# SpaceInvaders-v30.net
KiCad netlist of a schematic drawn in EAGLE
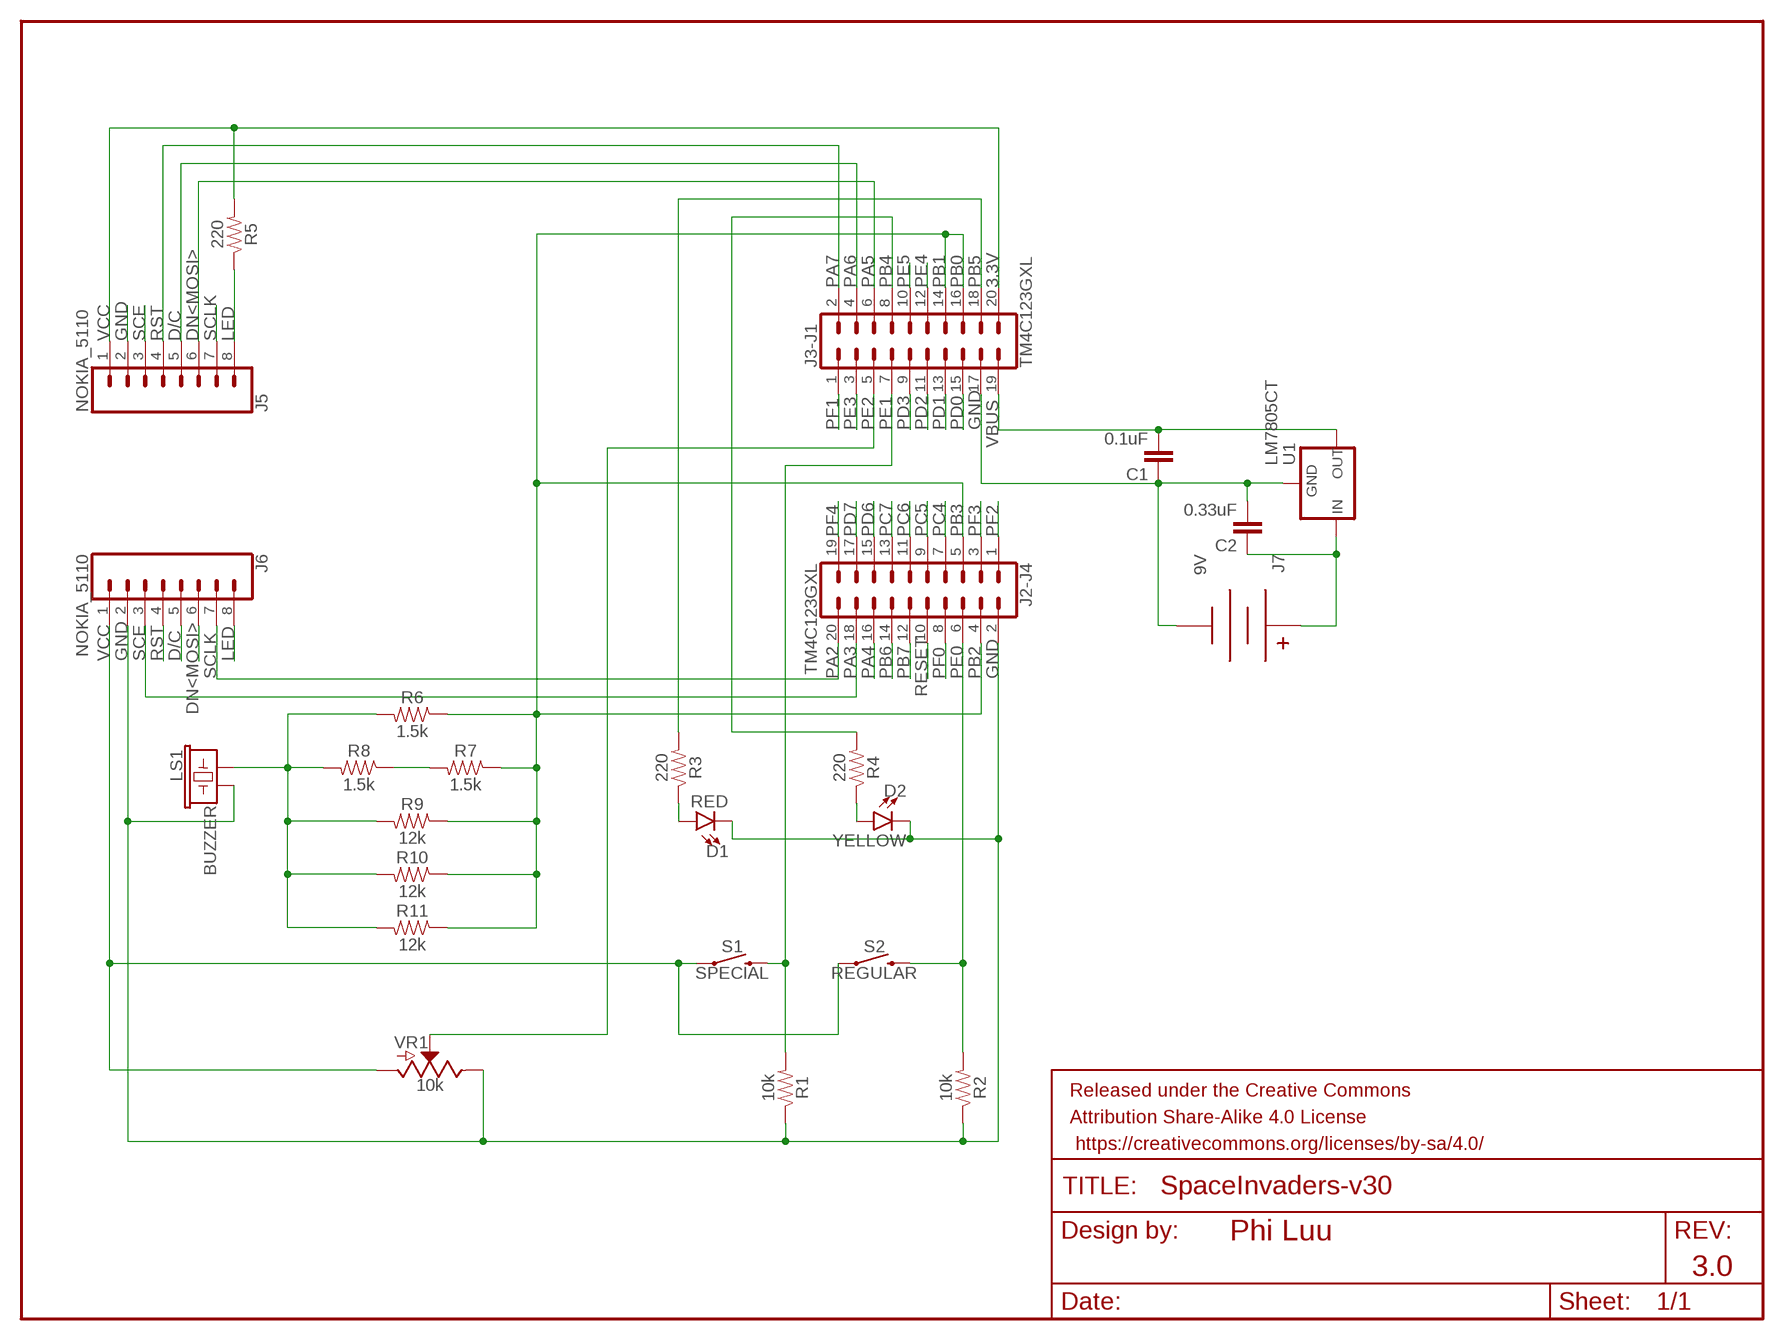
[diagram p0: schematic, sheet 1]

(export (version "E")
  (design (tool "Eeschema 10.0.6"))
  (components
    (comp (ref "C1")
      (value "0.1uF")
      (footprint "eagle-import:CAP-PTH-SMALL-KIT")
      (libsource (lib "eagle-import") (part "0.1UF-KIT-EZ-50V-20%"))
    )
    (comp (ref "C2")
      (value "0.33uF")
      (footprint "eagle-import:CAP-PTH-SMALL-KIT")
      (libsource (lib "eagle-import") (part "0.1UF-KIT-EZ-50V-20%"))
    )
    (comp (ref "D1")
      (value "RED")
      (footprint "eagle-import:LED_5MM")
      (libsource (lib "eagle-import") (part "LED5MM"))
    )
    (comp (ref "D2")
      (value "YELLOW")
      (footprint "eagle-import:LED_5MM")
      (libsource (lib "eagle-import") (part "LED5MM"))
    )
    (comp (ref "FRAME1")
      (value "FRAME-LETTER")
      (footprint "eagle-import:CREATIVE_COMMONS")
      (libsource (lib "eagle-import") (part "FRAME-LETTER"))
    )
    (comp (ref "J2-J4")
      (value "TM4C123GXL")
      (footprint "eagle-import:2X10")
      (libsource (lib "eagle-import") (part "CONN_10X2"))
    )
    (comp (ref "J3-J1")
      (value "TM4C123GXL")
      (footprint "eagle-import:2X10")
      (libsource (lib "eagle-import") (part "CONN_10X2"))
    )
    (comp (ref "J5")
      (value "NOKIA_5110")
      (footprint "eagle-import:1X08")
      (libsource (lib "eagle-import") (part "CONN_08{dblquote}"))
    )
    (comp (ref "J6")
      (value "NOKIA_5110")
      (footprint "eagle-import:1X08")
      (libsource (lib "eagle-import") (part "CONN_08{dblquote}"))
    )
    (comp (ref "J7")
      (value "9V")
      (footprint "eagle-import:BC9VPC")
      (libsource (lib "eagle-import") (part "BC9VPC"))
    )
    (comp (ref "LS1")
      (value "BUZZER")
      (footprint "eagle-import:BUZZER-12MM")
      (libsource (lib "eagle-import") (part "BUZZER-PTH"))
    )
    (comp (ref "R1")
      (value "10k")
      (footprint "eagle-import:AXIAL-0.3")
      (libsource (lib "eagle-import") (part "10KOHM-HORIZ-1/4W-5%"))
    )
    (comp (ref "R2")
      (value "10k")
      (footprint "eagle-import:AXIAL-0.3")
      (libsource (lib "eagle-import") (part "10KOHM-HORIZ-1/4W-5%"))
    )
    (comp (ref "R3")
      (value "220")
      (footprint "eagle-import:AXIAL-0.3")
      (libsource (lib "eagle-import") (part "1KOHM-HORIZ-1/4W-5%"))
    )
    (comp (ref "R4")
      (value "220")
      (footprint "eagle-import:AXIAL-0.3")
      (libsource (lib "eagle-import") (part "1KOHM-HORIZ-1/4W-5%"))
    )
    (comp (ref "R5")
      (value "220")
      (footprint "eagle-import:AXIAL-0.3")
      (libsource (lib "eagle-import") (part "1KOHM-HORIZ-1/4W-5%"))
    )
    (comp (ref "R6")
      (value "1.5k")
      (footprint "eagle-import:AXIAL-0.3")
      (libsource (lib "eagle-import") (part "1KOHM-HORIZ-1/4W-5%"))
    )
    (comp (ref "R7")
      (value "1.5k")
      (footprint "eagle-import:AXIAL-0.3")
      (libsource (lib "eagle-import") (part "1KOHM-HORIZ-1/4W-5%"))
    )
    (comp (ref "R8")
      (value "1.5k")
      (footprint "eagle-import:AXIAL-0.3")
      (libsource (lib "eagle-import") (part "1KOHM-HORIZ-1/4W-5%"))
    )
    (comp (ref "R9")
      (value "12k")
      (footprint "eagle-import:AXIAL-0.3")
      (libsource (lib "eagle-import") (part "1KOHM-HORIZ-1/4W-5%"))
    )
    (comp (ref "R10")
      (value "12k")
      (footprint "eagle-import:AXIAL-0.3")
      (libsource (lib "eagle-import") (part "1KOHM-HORIZ-1/4W-5%"))
    )
    (comp (ref "R11")
      (value "12k")
      (footprint "eagle-import:AXIAL-0.3")
      (libsource (lib "eagle-import") (part "1KOHM-HORIZ-1/4W-5%"))
    )
    (comp (ref "S1")
      (value "SPECIAL")
      (footprint "eagle-import:TACTILE_SWITCH_PTH_6.0MM")
      (libsource (lib "eagle-import") (part "MOMENTARY-SWITCH-SPST-PTH-6.0MM"))
    )
    (comp (ref "S2")
      (value "REGULAR")
      (footprint "eagle-import:TACTILE_SWITCH_PTH_6.0MM")
      (libsource (lib "eagle-import") (part "MOMENTARY-SWITCH-SPST-PTH-6.0MM"))
    )
    (comp (ref "U1")
      (value "LM7805CT")
      (footprint "eagle-import:TO-220-ALT")
      (libsource (lib "eagle-import") (part "V_REG_78XX-TO-220"))
    )
    (comp (ref "VR1")
      (value "10k")
      (footprint "eagle-import:SLIDER-MEDIUM")
      (libsource (lib "eagle-import") (part "POTENTIOMETER_SLIDE-30MM-1/10W-20%"))
    )
  )
  (nets
    (net (code "1") (name "/3.3V") (class "Default")
      (node (ref "J3-J1") (pin "20") (pinfunction "20_20") (pintype "passive"))
      (node (ref "J5") (pin "1") (pinfunction "1_1") (pintype "passive"))
      (node (ref "J6") (pin "1") (pinfunction "1_1") (pintype "passive"))
      (node (ref "R5") (pin "P$2") (pinfunction "2_P$2") (pintype "passive"))
      (node (ref "S1") (pin "1") (pinfunction "1_1") (pintype "passive"))
      (node (ref "S2") (pin "1") (pinfunction "1_1") (pintype "passive"))
      (node (ref "VR1") (pin "BOTTOM") (pinfunction "A_BOTTOM") (pintype "passive"))
    )
    (net (code "2") (name "/GND") (class "Default")
      (node (ref "C1") (pin "1") (pinfunction "1_1") (pintype "passive"))
      (node (ref "C2") (pin "2") (pinfunction "2_2") (pintype "passive"))
      (node (ref "D1") (pin "K") (pinfunction "C_K") (pintype "passive"))
      (node (ref "D2") (pin "K") (pinfunction "C_K") (pintype "passive"))
      (node (ref "J2-J4") (pin "2") (pinfunction "2_2") (pintype "passive"))
      (node (ref "J3-J1") (pin "17") (pinfunction "17_17") (pintype "passive"))
      (node (ref "J5") (pin "2") (pinfunction "2_2") (pintype "passive"))
      (node (ref "J6") (pin "2") (pinfunction "2_2") (pintype "passive"))
      (node (ref "J7") (pin "V-") (pinfunction "V-_V-") (pintype "bidirectional"))
      (node (ref "LS1") (pin "-") (pinfunction "2_-") (pintype "passive"))
      (node (ref "R1") (pin "P$1") (pinfunction "1_P$1") (pintype "passive"))
      (node (ref "R2") (pin "P$1") (pinfunction "1_P$1") (pintype "passive"))
      (node (ref "U1") (pin "GND") (pinfunction "GND_GND") (pintype "input"))
      (node (ref "VR1") (pin "TOP") (pinfunction "E_TOP") (pintype "passive"))
    )
    (net (code "3") (name "/LED") (class "Default")
      (node (ref "J5") (pin "8") (pinfunction "8_8") (pintype "passive"))
      (node (ref "J6") (pin "8") (pinfunction "8_8") (pintype "passive"))
      (node (ref "R5") (pin "P$1") (pinfunction "1_P$1") (pintype "passive"))
    )
    (net (code "4") (name "/PA2") (class "Default")
      (node (ref "J2-J4") (pin "20") (pinfunction "20_20") (pintype "passive"))
      (node (ref "J5") (pin "7") (pinfunction "7_7") (pintype "passive"))
      (node (ref "J6") (pin "7") (pinfunction "7_7") (pintype "passive"))
    )
    (net (code "5") (name "/PA3") (class "Default")
      (node (ref "J2-J4") (pin "18") (pinfunction "18_18") (pintype "passive"))
      (node (ref "J5") (pin "3") (pinfunction "3_3") (pintype "passive"))
      (node (ref "J6") (pin "3") (pinfunction "3_3") (pintype "passive"))
    )
    (net (code "6") (name "/PA4") (class "Default")
      (node (ref "J2-J4") (pin "16") (pinfunction "16_16") (pintype "passive"))
    )
    (net (code "7") (name "/PA5") (class "Default")
      (node (ref "J3-J1") (pin "6") (pinfunction "6_6") (pintype "passive"))
      (node (ref "J5") (pin "6") (pinfunction "6_6") (pintype "passive"))
      (node (ref "J6") (pin "6") (pinfunction "6_6") (pintype "passive"))
    )
    (net (code "8") (name "/PA6") (class "Default")
      (node (ref "J3-J1") (pin "4") (pinfunction "4_4") (pintype "passive"))
      (node (ref "J5") (pin "5") (pinfunction "5_5") (pintype "passive"))
      (node (ref "J6") (pin "5") (pinfunction "5_5") (pintype "passive"))
    )
    (net (code "9") (name "/PA7") (class "Default")
      (node (ref "J3-J1") (pin "2") (pinfunction "2_2") (pintype "passive"))
      (node (ref "J5") (pin "4") (pinfunction "4_4") (pintype "passive"))
      (node (ref "J6") (pin "4") (pinfunction "4_4") (pintype "passive"))
    )
    (net (code "10") (name "/PB4") (class "Default")
      (node (ref "J3-J1") (pin "8") (pinfunction "8_8") (pintype "passive"))
      (node (ref "R4") (pin "P$2") (pinfunction "2_P$2") (pintype "passive"))
    )
    (net (code "11") (name "/PB5") (class "Default")
      (node (ref "J3-J1") (pin "18") (pinfunction "18_18") (pintype "passive"))
      (node (ref "R3") (pin "P$2") (pinfunction "2_P$2") (pintype "passive"))
    )
    (net (code "12") (name "/PB6") (class "Default")
      (node (ref "J2-J4") (pin "14") (pinfunction "14_14") (pintype "passive"))
    )
    (net (code "13") (name "/PB7") (class "Default")
      (node (ref "J2-J4") (pin "12") (pinfunction "12_12") (pintype "passive"))
    )
    (net (code "14") (name "/PC4") (class "Default")
      (node (ref "J2-J4") (pin "7") (pinfunction "7_7") (pintype "passive"))
    )
    (net (code "15") (name "/PC5") (class "Default")
      (node (ref "J2-J4") (pin "9") (pinfunction "9_9") (pintype "passive"))
    )
    (net (code "16") (name "/PC6") (class "Default")
      (node (ref "J2-J4") (pin "11") (pinfunction "11_11") (pintype "passive"))
    )
    (net (code "17") (name "/PC7") (class "Default")
      (node (ref "J2-J4") (pin "13") (pinfunction "13_13") (pintype "passive"))
    )
    (net (code "18") (name "/PD0") (class "Default")
      (node (ref "J3-J1") (pin "15") (pinfunction "15_15") (pintype "passive"))
    )
    (net (code "19") (name "/PD1") (class "Default")
      (node (ref "J3-J1") (pin "13") (pinfunction "13_13") (pintype "passive"))
    )
    (net (code "20") (name "/PD2") (class "Default")
      (node (ref "J3-J1") (pin "11") (pinfunction "11_11") (pintype "passive"))
    )
    (net (code "21") (name "/PD3") (class "Default")
      (node (ref "J3-J1") (pin "9") (pinfunction "9_9") (pintype "passive"))
    )
    (net (code "22") (name "/PD6") (class "Default")
      (node (ref "J2-J4") (pin "15") (pinfunction "15_15") (pintype "passive"))
    )
    (net (code "23") (name "/PD7") (class "Default")
      (node (ref "J2-J4") (pin "17") (pinfunction "17_17") (pintype "passive"))
    )
    (net (code "24") (name "/PE0") (class "Default")
      (node (ref "J2-J4") (pin "6") (pinfunction "6_6") (pintype "passive"))
      (node (ref "R2") (pin "P$2") (pinfunction "2_P$2") (pintype "passive"))
      (node (ref "S2") (pin "3") (pinfunction "2_3") (pintype "passive"))
    )
    (net (code "25") (name "/PE1") (class "Default")
      (node (ref "J3-J1") (pin "7") (pinfunction "7_7") (pintype "passive"))
      (node (ref "R1") (pin "P$2") (pinfunction "2_P$2") (pintype "passive"))
      (node (ref "S1") (pin "3") (pinfunction "2_3") (pintype "passive"))
    )
    (net (code "26") (name "/PE2") (class "Default")
      (node (ref "J3-J1") (pin "5") (pinfunction "5_5") (pintype "passive"))
      (node (ref "VR1") (pin "WIPER") (pinfunction "S_WIPER") (pintype "passive"))
    )
    (net (code "27") (name "/PE3") (class "Default")
      (node (ref "J3-J1") (pin "3") (pinfunction "3_3") (pintype "passive"))
    )
    (net (code "28") (name "/PE4") (class "Default")
      (node (ref "J3-J1") (pin "12") (pinfunction "12_12") (pintype "passive"))
    )
    (net (code "29") (name "/PE5") (class "Default")
      (node (ref "J3-J1") (pin "10") (pinfunction "10_10") (pintype "passive"))
    )
    (net (code "30") (name "/PF0") (class "Default")
      (node (ref "J2-J4") (pin "8") (pinfunction "8_8") (pintype "passive"))
    )
    (net (code "31") (name "/PF1") (class "Default")
      (node (ref "J3-J1") (pin "1") (pinfunction "1_1") (pintype "passive"))
    )
    (net (code "32") (name "/PF2") (class "Default")
      (node (ref "J2-J4") (pin "1") (pinfunction "1_1") (pintype "passive"))
    )
    (net (code "33") (name "/PF3") (class "Default")
      (node (ref "J2-J4") (pin "3") (pinfunction "3_3") (pintype "passive"))
    )
    (net (code "34") (name "/PF4") (class "Default")
      (node (ref "J2-J4") (pin "19") (pinfunction "19_19") (pintype "passive"))
    )
    (net (code "35") (name "/RESET") (class "Default")
      (node (ref "J2-J4") (pin "10") (pinfunction "10_10") (pintype "passive"))
    )
    (net (code "36") (name "/VBUS") (class "Default")
      (node (ref "C1") (pin "2") (pinfunction "2_2") (pintype "passive"))
      (node (ref "J3-J1") (pin "19") (pinfunction "19_19") (pintype "passive"))
      (node (ref "U1") (pin "OUT") (pinfunction "OUT_OUT") (pintype "passive"))
    )
    (net (code "37") (name "Net-(C2-Pad1)") (class "Default")
      (node (ref "C2") (pin "1") (pinfunction "1_1") (pintype "passive"))
      (node (ref "J7") (pin "V+") (pinfunction "V+_V+") (pintype "bidirectional"))
      (node (ref "U1") (pin "IN") (pinfunction "IN_IN") (pintype "input"))
    )
    (net (code "38") (name "Net-(LS1-1)") (class "Default")
      (node (ref "LS1") (pin "+") (pinfunction "1_+") (pintype "passive"))
      (node (ref "R10") (pin "P$2") (pinfunction "2_P$2") (pintype "passive"))
      (node (ref "R11") (pin "P$2") (pinfunction "2_P$2") (pintype "passive"))
      (node (ref "R6") (pin "P$2") (pinfunction "2_P$2") (pintype "passive"))
      (node (ref "R8") (pin "P$2") (pinfunction "2_P$2") (pintype "passive"))
      (node (ref "R9") (pin "P$2") (pinfunction "2_P$2") (pintype "passive"))
    )
    (net (code "39") (name "Net-(R3-1)") (class "Default")
      (node (ref "D1") (pin "A") (pinfunction "A_A") (pintype "passive"))
      (node (ref "R3") (pin "P$1") (pinfunction "1_P$1") (pintype "passive"))
    )
    (net (code "40") (name "Net-(R4-1)") (class "Default")
      (node (ref "D2") (pin "A") (pinfunction "A_A") (pintype "passive"))
      (node (ref "R4") (pin "P$1") (pinfunction "1_P$1") (pintype "passive"))
    )
    (net (code "41") (name "Net-(R7-2)") (class "Default")
      (node (ref "R7") (pin "P$2") (pinfunction "2_P$2") (pintype "passive"))
      (node (ref "R8") (pin "P$1") (pinfunction "1_P$1") (pintype "passive"))
    )
    (net (code "42") (name "Net-(R10-1)") (class "Default")
      (node (ref "J2-J4") (pin "4") (pinfunction "4_4") (pintype "passive"))
      (node (ref "J2-J4") (pin "5") (pinfunction "5_5") (pintype "passive"))
      (node (ref "J3-J1") (pin "14") (pinfunction "14_14") (pintype "passive"))
      (node (ref "J3-J1") (pin "16") (pinfunction "16_16") (pintype "passive"))
      (node (ref "R10") (pin "P$1") (pinfunction "1_P$1") (pintype "passive"))
      (node (ref "R11") (pin "P$1") (pinfunction "1_P$1") (pintype "passive"))
      (node (ref "R6") (pin "P$1") (pinfunction "1_P$1") (pintype "passive"))
      (node (ref "R7") (pin "P$1") (pinfunction "1_P$1") (pintype "passive"))
      (node (ref "R9") (pin "P$1") (pinfunction "1_P$1") (pintype "passive"))
    )
  )
)
